# Main.net
KiCad netlist of a schematic drawn in Altium Designer
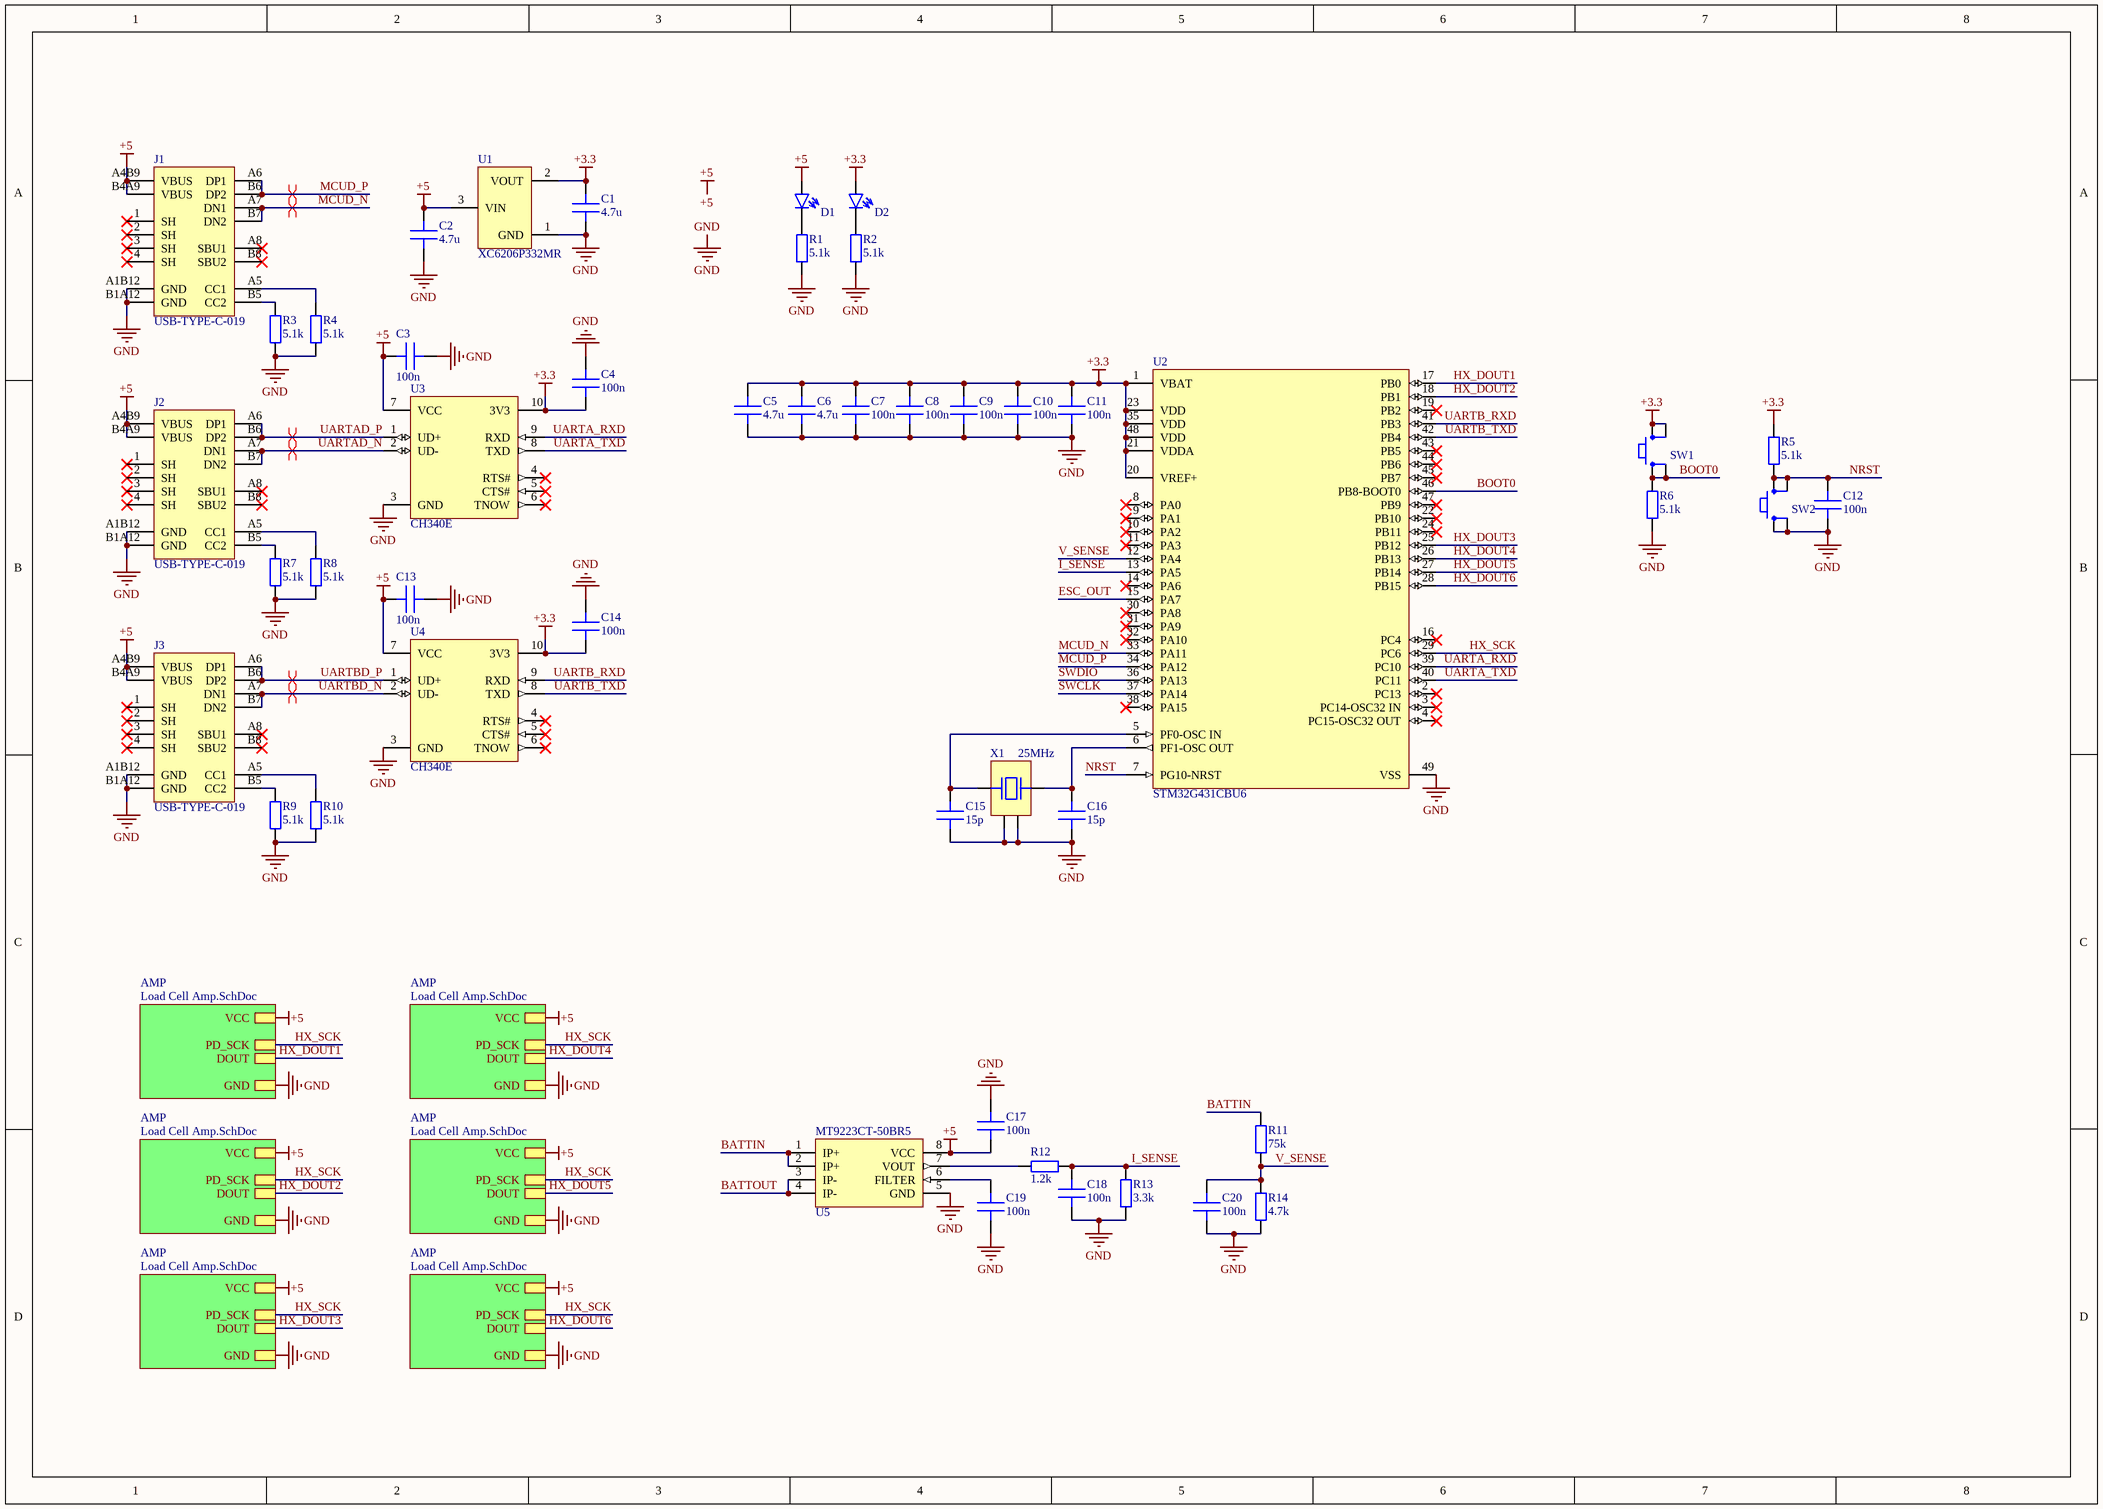
[diagram p0: Main.SchDoc]

(export (version "E")
  (design (tool "Eeschema 10.0.6"))
  (components
    (comp (ref "C1")
      (value "4.7u")
      (footprint "IPC C C0603 NO SILK")
      (libsource (lib "JLCPCB Library") (part "Generic CAP 0603"))
    )
    (comp (ref "C2")
      (value "4.7u")
      (footprint "IPC C C0603 NO SILK")
      (libsource (lib "JLCPCB Library") (part "Generic CAP 0603"))
    )
    (comp (ref "C3")
      (value "100n")
      (footprint "IPC C C0402 NO SILK")
      (libsource (lib "JLCPCB Library") (part "Generic CAP 0402"))
    )
    (comp (ref "C4")
      (value "100n")
      (footprint "IPC C C0402 NO SILK")
      (libsource (lib "JLCPCB Library") (part "Generic CAP 0402"))
    )
    (comp (ref "C5")
      (value "4.7u")
      (footprint "IPC C C0603 NO SILK")
      (libsource (lib "JLCPCB Library") (part "Generic CAP 0603"))
    )
    (comp (ref "C6")
      (value "4.7u")
      (footprint "IPC C C0603 NO SILK")
      (libsource (lib "JLCPCB Library") (part "Generic CAP 0603"))
    )
    (comp (ref "C7")
      (value "100n")
      (footprint "IPC C C0402 NO SILK")
      (libsource (lib "JLCPCB Library") (part "Generic CAP 0402"))
    )
    (comp (ref "C8")
      (value "100n")
      (footprint "IPC C C0402 NO SILK")
      (libsource (lib "JLCPCB Library") (part "Generic CAP 0402"))
    )
    (comp (ref "C9")
      (value "100n")
      (footprint "IPC C C0402 NO SILK")
      (libsource (lib "JLCPCB Library") (part "Generic CAP 0402"))
    )
    (comp (ref "C10")
      (value "100n")
      (footprint "IPC C C0402 NO SILK")
      (libsource (lib "JLCPCB Library") (part "Generic CAP 0402"))
    )
    (comp (ref "C11")
      (value "100n")
      (footprint "IPC C C0402 NO SILK")
      (libsource (lib "JLCPCB Library") (part "Generic CAP 0402"))
    )
    (comp (ref "C12")
      (value "100n")
      (footprint "IPC C C0402 NO SILK")
      (libsource (lib "JLCPCB Library") (part "Generic CAP 0402"))
    )
    (comp (ref "C13")
      (value "100n")
      (footprint "IPC C C0402 NO SILK")
      (libsource (lib "JLCPCB Library") (part "Generic CAP 0402"))
    )
    (comp (ref "C14")
      (value "100n")
      (footprint "IPC C C0402 NO SILK")
      (libsource (lib "JLCPCB Library") (part "Generic CAP 0402"))
    )
    (comp (ref "C15")
      (value "15p")
      (footprint "IPC C C0402 NO SILK")
      (libsource (lib "JLCPCB Library") (part "Generic CAP 0402"))
    )
    (comp (ref "C16")
      (value "15p")
      (footprint "IPC C C0402 NO SILK")
      (libsource (lib "JLCPCB Library") (part "Generic CAP 0402"))
    )
    (comp (ref "C17")
      (value "100n")
      (footprint "IPC C C0402 NO SILK")
      (libsource (lib "JLCPCB Library") (part "Generic CAP 0402"))
    )
    (comp (ref "C18")
      (value "100n")
      (footprint "IPC C C0402 NO SILK")
      (libsource (lib "JLCPCB Library") (part "Generic CAP 0402"))
    )
    (comp (ref "C19")
      (value "100n")
      (footprint "IPC C C0402 NO SILK")
      (libsource (lib "JLCPCB Library") (part "Generic CAP 0402"))
    )
    (comp (ref "C20")
      (value "100n")
      (footprint "IPC C C0402 NO SILK")
      (libsource (lib "JLCPCB Library") (part "Generic CAP 0402"))
    )
    (comp (ref "D1")
      (value "Generic LED 0603")
      (footprint "IPC C D0603")
      (libsource (lib "JLCPCB Library") (part "Generic LED 0603"))
    )
    (comp (ref "D2")
      (value "Generic LED 0603")
      (footprint "IPC C D0603")
      (libsource (lib "JLCPCB Library") (part "Generic LED 0603"))
    )
    (comp (ref "J1")
      (value "USB-TYPE-C-019")
      (footprint "USB-TYPE-C-12+4P")
      (fields (field (name "MANUFACTURER") "DEALON(德艺隆)"))
      (libsource (lib "JLCPCB Library") (part "USB-TYPE-C-019"))
    )
    (comp (ref "J2")
      (value "USB-TYPE-C-019")
      (footprint "USB-TYPE-C-12+4P")
      (fields (field (name "MANUFACTURER") "DEALON(德艺隆)"))
      (libsource (lib "JLCPCB Library") (part "USB-TYPE-C-019"))
    )
    (comp (ref "J3")
      (value "USB-TYPE-C-019")
      (footprint "USB-TYPE-C-12+4P")
      (fields (field (name "MANUFACTURER") "DEALON(德艺隆)"))
      (libsource (lib "JLCPCB Library") (part "USB-TYPE-C-019"))
    )
    (comp (ref "R1")
      (value "5.1k")
      (footprint "IPC C R0402 NO SILK")
      (libsource (lib "JLCPCB Library") (part "Generic RES 0402"))
    )
    (comp (ref "R2")
      (value "5.1k")
      (footprint "IPC C R0402 NO SILK")
      (libsource (lib "JLCPCB Library") (part "Generic RES 0402"))
    )
    (comp (ref "R3")
      (value "5.1k")
      (footprint "IPC C R0402 NO SILK")
      (libsource (lib "JLCPCB Library") (part "Generic RES 0402"))
    )
    (comp (ref "R4")
      (value "5.1k")
      (footprint "IPC C R0402 NO SILK")
      (libsource (lib "JLCPCB Library") (part "Generic RES 0402"))
    )
    (comp (ref "R5")
      (value "5.1k")
      (footprint "IPC C R0402 NO SILK")
      (libsource (lib "JLCPCB Library") (part "Generic RES 0402"))
    )
    (comp (ref "R6")
      (value "5.1k")
      (footprint "IPC C R0402 NO SILK")
      (libsource (lib "JLCPCB Library") (part "Generic RES 0402"))
    )
    (comp (ref "R7")
      (value "5.1k")
      (footprint "IPC C R0402 NO SILK")
      (libsource (lib "JLCPCB Library") (part "Generic RES 0402"))
    )
    (comp (ref "R8")
      (value "5.1k")
      (footprint "IPC C R0402 NO SILK")
      (libsource (lib "JLCPCB Library") (part "Generic RES 0402"))
    )
    (comp (ref "R9")
      (value "5.1k")
      (footprint "IPC C R0402 NO SILK")
      (libsource (lib "JLCPCB Library") (part "Generic RES 0402"))
    )
    (comp (ref "R10")
      (value "5.1k")
      (footprint "IPC C R0402 NO SILK")
      (libsource (lib "JLCPCB Library") (part "Generic RES 0402"))
    )
    (comp (ref "R11")
      (value "75k")
      (footprint "IPC C R0402 NO SILK")
      (libsource (lib "JLCPCB Library") (part "Generic RES 0402"))
    )
    (comp (ref "R12")
      (value "1.2k")
      (footprint "IPC C R0402 NO SILK")
      (libsource (lib "JLCPCB Library") (part "Generic RES 0402"))
    )
    (comp (ref "R13")
      (value "3.3k")
      (footprint "IPC C R0402 NO SILK")
      (libsource (lib "JLCPCB Library") (part "Generic RES 0402"))
    )
    (comp (ref "R14")
      (value "4.7k")
      (footprint "IPC C R0402 NO SILK")
      (libsource (lib "JLCPCB Library") (part "Generic RES 0402"))
    )
    (comp (ref "SW1")
      (value "TS-1187A-B-A-B")
      (footprint "TS-1187A-B-A-B")
      (libsource (lib "JLCPCB Library") (part "Push Button TS-1187A-B-A-B"))
    )
    (comp (ref "SW2")
      (value "TS-1187A-B-A-B")
      (footprint "TS-1187A-B-A-B")
      (libsource (lib "JLCPCB Library") (part "Push Button TS-1187A-B-A-B"))
    )
    (comp (ref "U1")
      (value "XC6206P332MR")
      (footprint "SOT23-3")
      (fields (field (name "MANUFACTURER") "TOREX(特瑞仕)"))
      (libsource (lib "JLCPCB Library") (part "3.3V Regulator XC6206P332MR_C5446"))
    )
    (comp (ref "U2")
      (value "STM32G431CBU6")
      (footprint "QFN50P700X700X60_HS-49L")
      (libsource (lib "JLCPCB Library") (part "STM32G431CBU6"))
    )
    (comp (ref "U3")
      (value "CH340E")
      (footprint "MSOP-UN10_L")
      (libsource (lib "JLCPCB Library") (part "CH340E"))
    )
    (comp (ref "U4")
      (value "CH340E")
      (footprint "MSOP-UN10_L")
      (libsource (lib "JLCPCB Library") (part "CH340E"))
    )
    (comp (ref "U5")
      (value "MT9223CT-50BR5")
      (footprint "SOP127P600X175-8L")
      (libsource (lib "JLCPCB Library") (part "MT9223CT-XXXR5"))
    )
    (comp (ref "X1")
      (value "25MHz")
      (footprint "OSC-SMD_4P-L3.2-W2.5-BL")
      (fields (field (name "MANUFACTURER") "YXC(扬兴晶振)") (field (name "MANUFACTURER PART") "X322525MOB4SI"))
      (libsource (lib "JLCPCB Library") (part "Crystal 25MHz X322525MOB4SI"))
    )
  )
  (nets
    (net (code "1") (name "+3.3") (class "Default")
      (node (ref "C1") (pin "2") (pinfunction "2_2") (pintype "passive"))
      (node (ref "C10") (pin "2") (pinfunction "2_2") (pintype "passive"))
      (node (ref "C11") (pin "2") (pinfunction "2_2") (pintype "passive"))
      (node (ref "C14") (pin "2") (pinfunction "2_2") (pintype "passive"))
      (node (ref "C4") (pin "2") (pinfunction "2_2") (pintype "passive"))
      (node (ref "C5") (pin "2") (pinfunction "2_2") (pintype "passive"))
      (node (ref "C6") (pin "2") (pinfunction "2_2") (pintype "passive"))
      (node (ref "C7") (pin "2") (pinfunction "2_2") (pintype "passive"))
      (node (ref "C8") (pin "2") (pinfunction "2_2") (pintype "passive"))
      (node (ref "C9") (pin "2") (pinfunction "2_2") (pintype "passive"))
      (node (ref "D2") (pin "1") (pinfunction "A_1") (pintype "passive"))
      (node (ref "R5") (pin "2") (pinfunction "2_2") (pintype "passive"))
      (node (ref "SW1") (pin "3") (pinfunction "3_3") (pintype "passive"))
      (node (ref "SW1") (pin "4") (pinfunction "4_4") (pintype "passive"))
      (node (ref "U1") (pin "2") (pinfunction "VOUT_2") (pintype "power_in"))
      (node (ref "U2") (pin "1") (pinfunction "VBAT_1") (pintype "power_in"))
      (node (ref "U2") (pin "20") (pinfunction "VREF+_20") (pintype "passive"))
      (node (ref "U2") (pin "21") (pinfunction "VDDA_21") (pintype "power_in"))
      (node (ref "U2") (pin "23") (pinfunction "VDD_23") (pintype "power_in"))
      (node (ref "U2") (pin "35") (pinfunction "VDD_35") (pintype "power_in"))
      (node (ref "U2") (pin "48") (pinfunction "VDD_48") (pintype "power_in"))
      (node (ref "U3") (pin "10") (pinfunction "3V3_10") (pintype "power_in"))
      (node (ref "U4") (pin "10") (pinfunction "3V3_10") (pintype "power_in"))
    )
    (net (code "2") (name "+5") (class "Default")
      (node (ref "C13") (pin "2") (pinfunction "2_2") (pintype "passive"))
      (node (ref "C17") (pin "2") (pinfunction "2_2") (pintype "passive"))
      (node (ref "C2") (pin "2") (pinfunction "2_2") (pintype "passive"))
      (node (ref "C3") (pin "2") (pinfunction "2_2") (pintype "passive"))
      (node (ref "D1") (pin "1") (pinfunction "A_1") (pintype "passive"))
      (node (ref "J1") (pin "A4B9") (pinfunction "VBUS_A4B9") (pintype "power_in"))
      (node (ref "J1") (pin "B4A9") (pinfunction "VBUS_B4A9") (pintype "power_in"))
      (node (ref "J2") (pin "A4B9") (pinfunction "VBUS_A4B9") (pintype "power_in"))
      (node (ref "J2") (pin "B4A9") (pinfunction "VBUS_B4A9") (pintype "power_in"))
      (node (ref "J3") (pin "A4B9") (pinfunction "VBUS_A4B9") (pintype "power_in"))
      (node (ref "J3") (pin "B4A9") (pinfunction "VBUS_B4A9") (pintype "power_in"))
      (node (ref "U1") (pin "3") (pinfunction "VIN_3") (pintype "power_in"))
      (node (ref "U3") (pin "7") (pinfunction "VCC_7") (pintype "power_in"))
      (node (ref "U4") (pin "7") (pinfunction "VCC_7") (pintype "power_in"))
      (node (ref "U5") (pin "8") (pinfunction "VCC_8") (pintype "power_in"))
    )
    (net (code "3") (name "/BATTIN") (class "Default")
      (node (ref "R11") (pin "2") (pinfunction "2_2") (pintype "passive"))
      (node (ref "U5") (pin "1") (pinfunction "IP+_1") (pintype "passive"))
      (node (ref "U5") (pin "2") (pinfunction "IP+_2") (pintype "passive"))
    )
    (net (code "4") (name "/BATTOUT") (class "Default")
      (node (ref "U5") (pin "3") (pinfunction "IP-_3") (pintype "passive"))
      (node (ref "U5") (pin "4") (pinfunction "IP-_4") (pintype "passive"))
    )
    (net (code "5") (name "/BOOT0") (class "Default")
      (node (ref "R6") (pin "1") (pinfunction "1_1") (pintype "passive"))
      (node (ref "SW1") (pin "1") (pinfunction "1_1") (pintype "passive"))
      (node (ref "SW1") (pin "2") (pinfunction "2_2") (pintype "passive"))
      (node (ref "U2") (pin "46") (pinfunction "PB8-BOOT0_46") (pintype "bidirectional"))
    )
    (net (code "6") (name "/ESC_OUT") (class "Default")
      (node (ref "U2") (pin "15") (pinfunction "PA7_15") (pintype "bidirectional"))
    )
    (net (code "7") (name "/HX_DOUT1") (class "Default")
      (node (ref "U2") (pin "17") (pinfunction "PB0_17") (pintype "bidirectional"))
    )
    (net (code "8") (name "/HX_DOUT2") (class "Default")
      (node (ref "U2") (pin "18") (pinfunction "PB1_18") (pintype "bidirectional"))
    )
    (net (code "9") (name "/HX_DOUT3") (class "Default")
      (node (ref "U2") (pin "25") (pinfunction "PB12_25") (pintype "bidirectional"))
    )
    (net (code "10") (name "/HX_DOUT4") (class "Default")
      (node (ref "U2") (pin "26") (pinfunction "PB13_26") (pintype "bidirectional"))
    )
    (net (code "11") (name "/HX_DOUT5") (class "Default")
      (node (ref "U2") (pin "27") (pinfunction "PB14_27") (pintype "bidirectional"))
    )
    (net (code "12") (name "/HX_DOUT6") (class "Default")
      (node (ref "U2") (pin "28") (pinfunction "PB15_28") (pintype "bidirectional"))
    )
    (net (code "13") (name "/HX_SCK") (class "Default")
      (node (ref "U2") (pin "29") (pinfunction "PC6_29") (pintype "bidirectional"))
    )
    (net (code "14") (name "/I_SENSE") (class "Default")
      (node (ref "C18") (pin "2") (pinfunction "2_2") (pintype "passive"))
      (node (ref "R12") (pin "1") (pinfunction "1_1") (pintype "passive"))
      (node (ref "R13") (pin "2") (pinfunction "2_2") (pintype "passive"))
      (node (ref "U2") (pin "13") (pinfunction "PA5_13") (pintype "bidirectional"))
    )
    (net (code "15") (name "/MCUD_N") (class "Default")
      (node (ref "J1") (pin "A7") (pinfunction "DN1_A7") (pintype "passive"))
      (node (ref "J1") (pin "B7") (pinfunction "DN2_B7") (pintype "passive"))
      (node (ref "U2") (pin "33") (pinfunction "PA11_33") (pintype "bidirectional"))
    )
    (net (code "16") (name "/MCUD_P") (class "Default")
      (node (ref "J1") (pin "A6") (pinfunction "DP1_A6") (pintype "passive"))
      (node (ref "J1") (pin "B6") (pinfunction "DP2_B6") (pintype "passive"))
      (node (ref "U2") (pin "34") (pinfunction "PA12_34") (pintype "bidirectional"))
    )
    (net (code "17") (name "/NRST") (class "Default")
      (node (ref "C12") (pin "2") (pinfunction "2_2") (pintype "passive"))
      (node (ref "R5") (pin "1") (pinfunction "1_1") (pintype "passive"))
      (node (ref "SW2") (pin "3") (pinfunction "3_3") (pintype "passive"))
      (node (ref "SW2") (pin "4") (pinfunction "4_4") (pintype "passive"))
      (node (ref "U2") (pin "7") (pinfunction "PG10-NRST_7") (pintype "input"))
    )
    (net (code "18") (name "/SWCLK") (class "Default")
      (node (ref "U2") (pin "37") (pinfunction "PA14_37") (pintype "bidirectional"))
    )
    (net (code "19") (name "/SWDIO") (class "Default")
      (node (ref "U2") (pin "36") (pinfunction "PA13_36") (pintype "bidirectional"))
    )
    (net (code "20") (name "/UARTAD_N") (class "Default")
      (node (ref "J2") (pin "A7") (pinfunction "DN1_A7") (pintype "passive"))
      (node (ref "J2") (pin "B7") (pinfunction "DN2_B7") (pintype "passive"))
      (node (ref "U3") (pin "2") (pinfunction "UD-_2") (pintype "bidirectional"))
    )
    (net (code "21") (name "/UARTAD_P") (class "Default")
      (node (ref "J2") (pin "A6") (pinfunction "DP1_A6") (pintype "passive"))
      (node (ref "J2") (pin "B6") (pinfunction "DP2_B6") (pintype "passive"))
      (node (ref "U3") (pin "1") (pinfunction "UD+_1") (pintype "bidirectional"))
    )
    (net (code "22") (name "/UARTA_RXD") (class "Default")
      (node (ref "U2") (pin "39") (pinfunction "PC10_39") (pintype "bidirectional"))
      (node (ref "U3") (pin "9") (pinfunction "RXD_9") (pintype "input"))
    )
    (net (code "23") (name "/UARTA_TXD") (class "Default")
      (node (ref "U2") (pin "40") (pinfunction "PC11_40") (pintype "bidirectional"))
      (node (ref "U3") (pin "8") (pinfunction "TXD_8") (pintype "output"))
    )
    (net (code "24") (name "/UARTBD_N") (class "Default")
      (node (ref "J3") (pin "A7") (pinfunction "DN1_A7") (pintype "passive"))
      (node (ref "J3") (pin "B7") (pinfunction "DN2_B7") (pintype "passive"))
      (node (ref "U4") (pin "2") (pinfunction "UD-_2") (pintype "bidirectional"))
    )
    (net (code "25") (name "/UARTBD_P") (class "Default")
      (node (ref "J3") (pin "A6") (pinfunction "DP1_A6") (pintype "passive"))
      (node (ref "J3") (pin "B6") (pinfunction "DP2_B6") (pintype "passive"))
      (node (ref "U4") (pin "1") (pinfunction "UD+_1") (pintype "bidirectional"))
    )
    (net (code "26") (name "/UARTB_RXD") (class "Default")
      (node (ref "U2") (pin "41") (pinfunction "PB3_41") (pintype "bidirectional"))
      (node (ref "U4") (pin "9") (pinfunction "RXD_9") (pintype "input"))
    )
    (net (code "27") (name "/UARTB_TXD") (class "Default")
      (node (ref "U2") (pin "42") (pinfunction "PB4_42") (pintype "bidirectional"))
      (node (ref "U4") (pin "8") (pinfunction "TXD_8") (pintype "output"))
    )
    (net (code "28") (name "/V_SENSE") (class "Default")
      (node (ref "C20") (pin "2") (pinfunction "2_2") (pintype "passive"))
      (node (ref "R11") (pin "1") (pinfunction "1_1") (pintype "passive"))
      (node (ref "R14") (pin "2") (pinfunction "2_2") (pintype "passive"))
      (node (ref "U2") (pin "12") (pinfunction "PA4_12") (pintype "bidirectional"))
    )
    (net (code "29") (name "GND") (class "Default")
      (node (ref "C1") (pin "1") (pinfunction "1_1") (pintype "passive"))
      (node (ref "C10") (pin "1") (pinfunction "1_1") (pintype "passive"))
      (node (ref "C11") (pin "1") (pinfunction "1_1") (pintype "passive"))
      (node (ref "C12") (pin "1") (pinfunction "1_1") (pintype "passive"))
      (node (ref "C13") (pin "1") (pinfunction "1_1") (pintype "passive"))
      (node (ref "C14") (pin "1") (pinfunction "1_1") (pintype "passive"))
      (node (ref "C15") (pin "1") (pinfunction "1_1") (pintype "passive"))
      (node (ref "C16") (pin "1") (pinfunction "1_1") (pintype "passive"))
      (node (ref "C17") (pin "1") (pinfunction "1_1") (pintype "passive"))
      (node (ref "C18") (pin "1") (pinfunction "1_1") (pintype "passive"))
      (node (ref "C19") (pin "1") (pinfunction "1_1") (pintype "passive"))
      (node (ref "C2") (pin "1") (pinfunction "1_1") (pintype "passive"))
      (node (ref "C20") (pin "1") (pinfunction "1_1") (pintype "passive"))
      (node (ref "C3") (pin "1") (pinfunction "1_1") (pintype "passive"))
      (node (ref "C4") (pin "1") (pinfunction "1_1") (pintype "passive"))
      (node (ref "C5") (pin "1") (pinfunction "1_1") (pintype "passive"))
      (node (ref "C6") (pin "1") (pinfunction "1_1") (pintype "passive"))
      (node (ref "C7") (pin "1") (pinfunction "1_1") (pintype "passive"))
      (node (ref "C8") (pin "1") (pinfunction "1_1") (pintype "passive"))
      (node (ref "C9") (pin "1") (pinfunction "1_1") (pintype "passive"))
      (node (ref "J1") (pin "A1B12") (pinfunction "GND_A1B12") (pintype "power_in"))
      (node (ref "J1") (pin "B1A12") (pinfunction "GND_B1A12") (pintype "power_in"))
      (node (ref "J2") (pin "A1B12") (pinfunction "GND_A1B12") (pintype "power_in"))
      (node (ref "J2") (pin "B1A12") (pinfunction "GND_B1A12") (pintype "power_in"))
      (node (ref "J3") (pin "A1B12") (pinfunction "GND_A1B12") (pintype "power_in"))
      (node (ref "J3") (pin "B1A12") (pinfunction "GND_B1A12") (pintype "power_in"))
      (node (ref "R1") (pin "1") (pinfunction "1_1") (pintype "passive"))
      (node (ref "R10") (pin "1") (pinfunction "1_1") (pintype "passive"))
      (node (ref "R13") (pin "1") (pinfunction "1_1") (pintype "passive"))
      (node (ref "R14") (pin "1") (pinfunction "1_1") (pintype "passive"))
      (node (ref "R2") (pin "1") (pinfunction "1_1") (pintype "passive"))
      (node (ref "R3") (pin "1") (pinfunction "1_1") (pintype "passive"))
      (node (ref "R4") (pin "1") (pinfunction "1_1") (pintype "passive"))
      (node (ref "R6") (pin "2") (pinfunction "2_2") (pintype "passive"))
      (node (ref "R7") (pin "1") (pinfunction "1_1") (pintype "passive"))
      (node (ref "R8") (pin "1") (pinfunction "1_1") (pintype "passive"))
      (node (ref "R9") (pin "1") (pinfunction "1_1") (pintype "passive"))
      (node (ref "SW2") (pin "1") (pinfunction "1_1") (pintype "passive"))
      (node (ref "SW2") (pin "2") (pinfunction "2_2") (pintype "passive"))
      (node (ref "U1") (pin "1") (pinfunction "GND_1") (pintype "power_in"))
      (node (ref "U2") (pin "49") (pinfunction "VSS_49") (pintype "power_in"))
      (node (ref "U3") (pin "3") (pinfunction "GND_3") (pintype "power_in"))
      (node (ref "U4") (pin "3") (pinfunction "GND_3") (pintype "power_in"))
      (node (ref "U5") (pin "5") (pinfunction "GND_5") (pintype "power_in"))
      (node (ref "X1") (pin "2") (pinfunction "2_2") (pintype "passive"))
      (node (ref "X1") (pin "4") (pinfunction "4_4") (pintype "passive"))
    )
    (net (code "30") (name "Net-(D1-C)") (class "Default")
      (node (ref "D1") (pin "2") (pinfunction "C_2") (pintype "passive"))
      (node (ref "R1") (pin "2") (pinfunction "2_2") (pintype "passive"))
    )
    (net (code "31") (name "Net-(D2-C)") (class "Default")
      (node (ref "D2") (pin "2") (pinfunction "C_2") (pintype "passive"))
      (node (ref "R2") (pin "2") (pinfunction "2_2") (pintype "passive"))
    )
    (net (code "32") (name "Net-(J1-CC1)") (class "Default")
      (node (ref "J1") (pin "A5") (pinfunction "CC1_A5") (pintype "passive"))
      (node (ref "R4") (pin "2") (pinfunction "2_2") (pintype "passive"))
    )
    (net (code "33") (name "Net-(J1-CC2)") (class "Default")
      (node (ref "J1") (pin "B5") (pinfunction "CC2_B5") (pintype "passive"))
      (node (ref "R3") (pin "2") (pinfunction "2_2") (pintype "passive"))
    )
    (net (code "34") (name "Net-(J2-CC1)") (class "Default")
      (node (ref "J2") (pin "A5") (pinfunction "CC1_A5") (pintype "passive"))
      (node (ref "R8") (pin "2") (pinfunction "2_2") (pintype "passive"))
    )
    (net (code "35") (name "Net-(J2-CC2)") (class "Default")
      (node (ref "J2") (pin "B5") (pinfunction "CC2_B5") (pintype "passive"))
      (node (ref "R7") (pin "2") (pinfunction "2_2") (pintype "passive"))
    )
    (net (code "36") (name "Net-(J3-CC1)") (class "Default")
      (node (ref "J3") (pin "A5") (pinfunction "CC1_A5") (pintype "passive"))
      (node (ref "R10") (pin "2") (pinfunction "2_2") (pintype "passive"))
    )
    (net (code "37") (name "Net-(J3-CC2)") (class "Default")
      (node (ref "J3") (pin "B5") (pinfunction "CC2_B5") (pintype "passive"))
      (node (ref "R9") (pin "2") (pinfunction "2_2") (pintype "passive"))
    )
    (net (code "38") (name "Net-(U2-PF0-OSC_IN)") (class "Default")
      (node (ref "C15") (pin "2") (pinfunction "2_2") (pintype "passive"))
      (node (ref "U2") (pin "5") (pinfunction "PF0-OSC_IN_5") (pintype "input"))
      (node (ref "X1") (pin "1") (pinfunction "1_1") (pintype "passive"))
    )
    (net (code "39") (name "Net-(U2-PF1-OSC_OUT)") (class "Default")
      (node (ref "C16") (pin "2") (pinfunction "2_2") (pintype "passive"))
      (node (ref "U2") (pin "6") (pinfunction "PF1-OSC_OUT_6") (pintype "output"))
      (node (ref "X1") (pin "3") (pinfunction "3_3") (pintype "passive"))
    )
    (net (code "40") (name "Net-(U5-FILTER)") (class "Default")
      (node (ref "C19") (pin "2") (pinfunction "2_2") (pintype "passive"))
      (node (ref "U5") (pin "6") (pinfunction "FILTER_6") (pintype "input"))
    )
    (net (code "41") (name "Net-(U5-VOUT)") (class "Default")
      (node (ref "R12") (pin "2") (pinfunction "2_2") (pintype "passive"))
      (node (ref "U5") (pin "7") (pinfunction "VOUT_7") (pintype "output"))
    )
    (net (code "42") (name "unconnected-(J1-SBU1-PadA8)") (class "Default")
      (node (ref "J1") (pin "A8") (pinfunction "SBU1_A8") (pintype "passive+no_connect"))
    )
    (net (code "43") (name "unconnected-(J1-SBU2-PadB8)") (class "Default")
      (node (ref "J1") (pin "B8") (pinfunction "SBU2_B8") (pintype "passive+no_connect"))
    )
    (net (code "44") (name "unconnected-(J1-SH-Pad1)") (class "Default")
      (node (ref "J1") (pin "1") (pinfunction "SH_1") (pintype "passive+no_connect"))
    )
    (net (code "45") (name "unconnected-(J1-SH-Pad2)") (class "Default")
      (node (ref "J1") (pin "2") (pinfunction "SH_2") (pintype "passive+no_connect"))
    )
    (net (code "46") (name "unconnected-(J1-SH-Pad3)") (class "Default")
      (node (ref "J1") (pin "3") (pinfunction "SH_3") (pintype "passive+no_connect"))
    )
    (net (code "47") (name "unconnected-(J1-SH-Pad4)") (class "Default")
      (node (ref "J1") (pin "4") (pinfunction "SH_4") (pintype "passive+no_connect"))
    )
    (net (code "48") (name "unconnected-(J2-SBU1-PadA8)") (class "Default")
      (node (ref "J2") (pin "A8") (pinfunction "SBU1_A8") (pintype "passive+no_connect"))
    )
    (net (code "49") (name "unconnected-(J2-SBU2-PadB8)") (class "Default")
      (node (ref "J2") (pin "B8") (pinfunction "SBU2_B8") (pintype "passive+no_connect"))
    )
    (net (code "50") (name "unconnected-(J2-SH-Pad1)") (class "Default")
      (node (ref "J2") (pin "1") (pinfunction "SH_1") (pintype "passive+no_connect"))
    )
    (net (code "51") (name "unconnected-(J2-SH-Pad2)") (class "Default")
      (node (ref "J2") (pin "2") (pinfunction "SH_2") (pintype "passive+no_connect"))
    )
    (net (code "52") (name "unconnected-(J2-SH-Pad3)") (class "Default")
      (node (ref "J2") (pin "3") (pinfunction "SH_3") (pintype "passive+no_connect"))
    )
    (net (code "53") (name "unconnected-(J2-SH-Pad4)") (class "Default")
      (node (ref "J2") (pin "4") (pinfunction "SH_4") (pintype "passive+no_connect"))
    )
    (net (code "54") (name "unconnected-(J3-SBU1-PadA8)") (class "Default")
      (node (ref "J3") (pin "A8") (pinfunction "SBU1_A8") (pintype "passive+no_connect"))
    )
    (net (code "55") (name "unconnected-(J3-SBU2-PadB8)") (class "Default")
      (node (ref "J3") (pin "B8") (pinfunction "SBU2_B8") (pintype "passive+no_connect"))
    )
    (net (code "56") (name "unconnected-(J3-SH-Pad1)") (class "Default")
      (node (ref "J3") (pin "1") (pinfunction "SH_1") (pintype "passive+no_connect"))
    )
    (net (code "57") (name "unconnected-(J3-SH-Pad2)") (class "Default")
      (node (ref "J3") (pin "2") (pinfunction "SH_2") (pintype "passive+no_connect"))
    )
    (net (code "58") (name "unconnected-(J3-SH-Pad3)") (class "Default")
      (node (ref "J3") (pin "3") (pinfunction "SH_3") (pintype "passive+no_connect"))
    )
    (net (code "59") (name "unconnected-(J3-SH-Pad4)") (class "Default")
      (node (ref "J3") (pin "4") (pinfunction "SH_4") (pintype "passive+no_connect"))
    )
    (net (code "60") (name "unconnected-(U2-PA0-Pad8)") (class "Default")
      (node (ref "U2") (pin "8") (pinfunction "PA0_8") (pintype "bidirectional+no_connect"))
    )
    (net (code "61") (name "unconnected-(U2-PA1-Pad9)") (class "Default")
      (node (ref "U2") (pin "9") (pinfunction "PA1_9") (pintype "bidirectional+no_connect"))
    )
    (net (code "62") (name "unconnected-(U2-PA2-Pad10)") (class "Default")
      (node (ref "U2") (pin "10") (pinfunction "PA2_10") (pintype "bidirectional+no_connect"))
    )
    (net (code "63") (name "unconnected-(U2-PA3-Pad11)") (class "Default")
      (node (ref "U2") (pin "11") (pinfunction "PA3_11") (pintype "bidirectional+no_connect"))
    )
    (net (code "64") (name "unconnected-(U2-PA6-Pad14)") (class "Default")
      (node (ref "U2") (pin "14") (pinfunction "PA6_14") (pintype "bidirectional+no_connect"))
    )
    (net (code "65") (name "unconnected-(U2-PA8-Pad30)") (class "Default")
      (node (ref "U2") (pin "30") (pinfunction "PA8_30") (pintype "bidirectional+no_connect"))
    )
    (net (code "66") (name "unconnected-(U2-PA9-Pad31)") (class "Default")
      (node (ref "U2") (pin "31") (pinfunction "PA9_31") (pintype "bidirectional+no_connect"))
    )
    (net (code "67") (name "unconnected-(U2-PA10-Pad32)") (class "Default")
      (node (ref "U2") (pin "32") (pinfunction "PA10_32") (pintype "bidirectional+no_connect"))
    )
    (net (code "68") (name "unconnected-(U2-PA15-Pad38)") (class "Default")
      (node (ref "U2") (pin "38") (pinfunction "PA15_38") (pintype "bidirectional+no_connect"))
    )
    (net (code "69") (name "unconnected-(U2-PB2-Pad19)") (class "Default")
      (node (ref "U2") (pin "19") (pinfunction "PB2_19") (pintype "bidirectional+no_connect"))
    )
    (net (code "70") (name "unconnected-(U2-PB5-Pad43)") (class "Default")
      (node (ref "U2") (pin "43") (pinfunction "PB5_43") (pintype "bidirectional+no_connect"))
    )
    (net (code "71") (name "unconnected-(U2-PB6-Pad44)") (class "Default")
      (node (ref "U2") (pin "44") (pinfunction "PB6_44") (pintype "bidirectional+no_connect"))
    )
    (net (code "72") (name "unconnected-(U2-PB7-Pad45)") (class "Default")
      (node (ref "U2") (pin "45") (pinfunction "PB7_45") (pintype "bidirectional+no_connect"))
    )
    (net (code "73") (name "unconnected-(U2-PB9-Pad47)") (class "Default")
      (node (ref "U2") (pin "47") (pinfunction "PB9_47") (pintype "bidirectional+no_connect"))
    )
    (net (code "74") (name "unconnected-(U2-PB10-Pad22)") (class "Default")
      (node (ref "U2") (pin "22") (pinfunction "PB10_22") (pintype "bidirectional+no_connect"))
    )
    (net (code "75") (name "unconnected-(U2-PB11-Pad24)") (class "Default")
      (node (ref "U2") (pin "24") (pinfunction "PB11_24") (pintype "bidirectional+no_connect"))
    )
    (net (code "76") (name "unconnected-(U2-PC4-Pad16)") (class "Default")
      (node (ref "U2") (pin "16") (pinfunction "PC4_16") (pintype "bidirectional+no_connect"))
    )
    (net (code "77") (name "unconnected-(U2-PC13-Pad2)") (class "Default")
      (node (ref "U2") (pin "2") (pinfunction "PC13_2") (pintype "bidirectional+no_connect"))
    )
    (net (code "78") (name "unconnected-(U2-PC14-OSC32_IN-Pad3)") (class "Default")
      (node (ref "U2") (pin "3") (pinfunction "PC14-OSC32_IN_3") (pintype "bidirectional+no_connect"))
    )
    (net (code "79") (name "unconnected-(U2-PC15-OSC32_OUT-Pad4)") (class "Default")
      (node (ref "U2") (pin "4") (pinfunction "PC15-OSC32_OUT_4") (pintype "bidirectional+no_connect"))
    )
    (net (code "80") (name "unconnected-(U3-CTS#-Pad5)") (class "Default")
      (node (ref "U3") (pin "5") (pinfunction "CTS#_5") (pintype "input+no_connect"))
    )
    (net (code "81") (name "unconnected-(U3-RTS#-Pad4)") (class "Default")
      (node (ref "U3") (pin "4") (pinfunction "RTS#_4") (pintype "output+no_connect"))
    )
    (net (code "82") (name "unconnected-(U3-TNOW-Pad6)") (class "Default")
      (node (ref "U3") (pin "6") (pinfunction "TNOW_6") (pintype "output+no_connect"))
    )
    (net (code "83") (name "unconnected-(U4-CTS#-Pad5)") (class "Default")
      (node (ref "U4") (pin "5") (pinfunction "CTS#_5") (pintype "input+no_connect"))
    )
    (net (code "84") (name "unconnected-(U4-RTS#-Pad4)") (class "Default")
      (node (ref "U4") (pin "4") (pinfunction "RTS#_4") (pintype "output+no_connect"))
    )
    (net (code "85") (name "unconnected-(U4-TNOW-Pad6)") (class "Default")
      (node (ref "U4") (pin "6") (pinfunction "TNOW_6") (pintype "output+no_connect"))
    )
  )
)
